# clock.net
KiCad netlist of a schematic drawn in Altium Designer
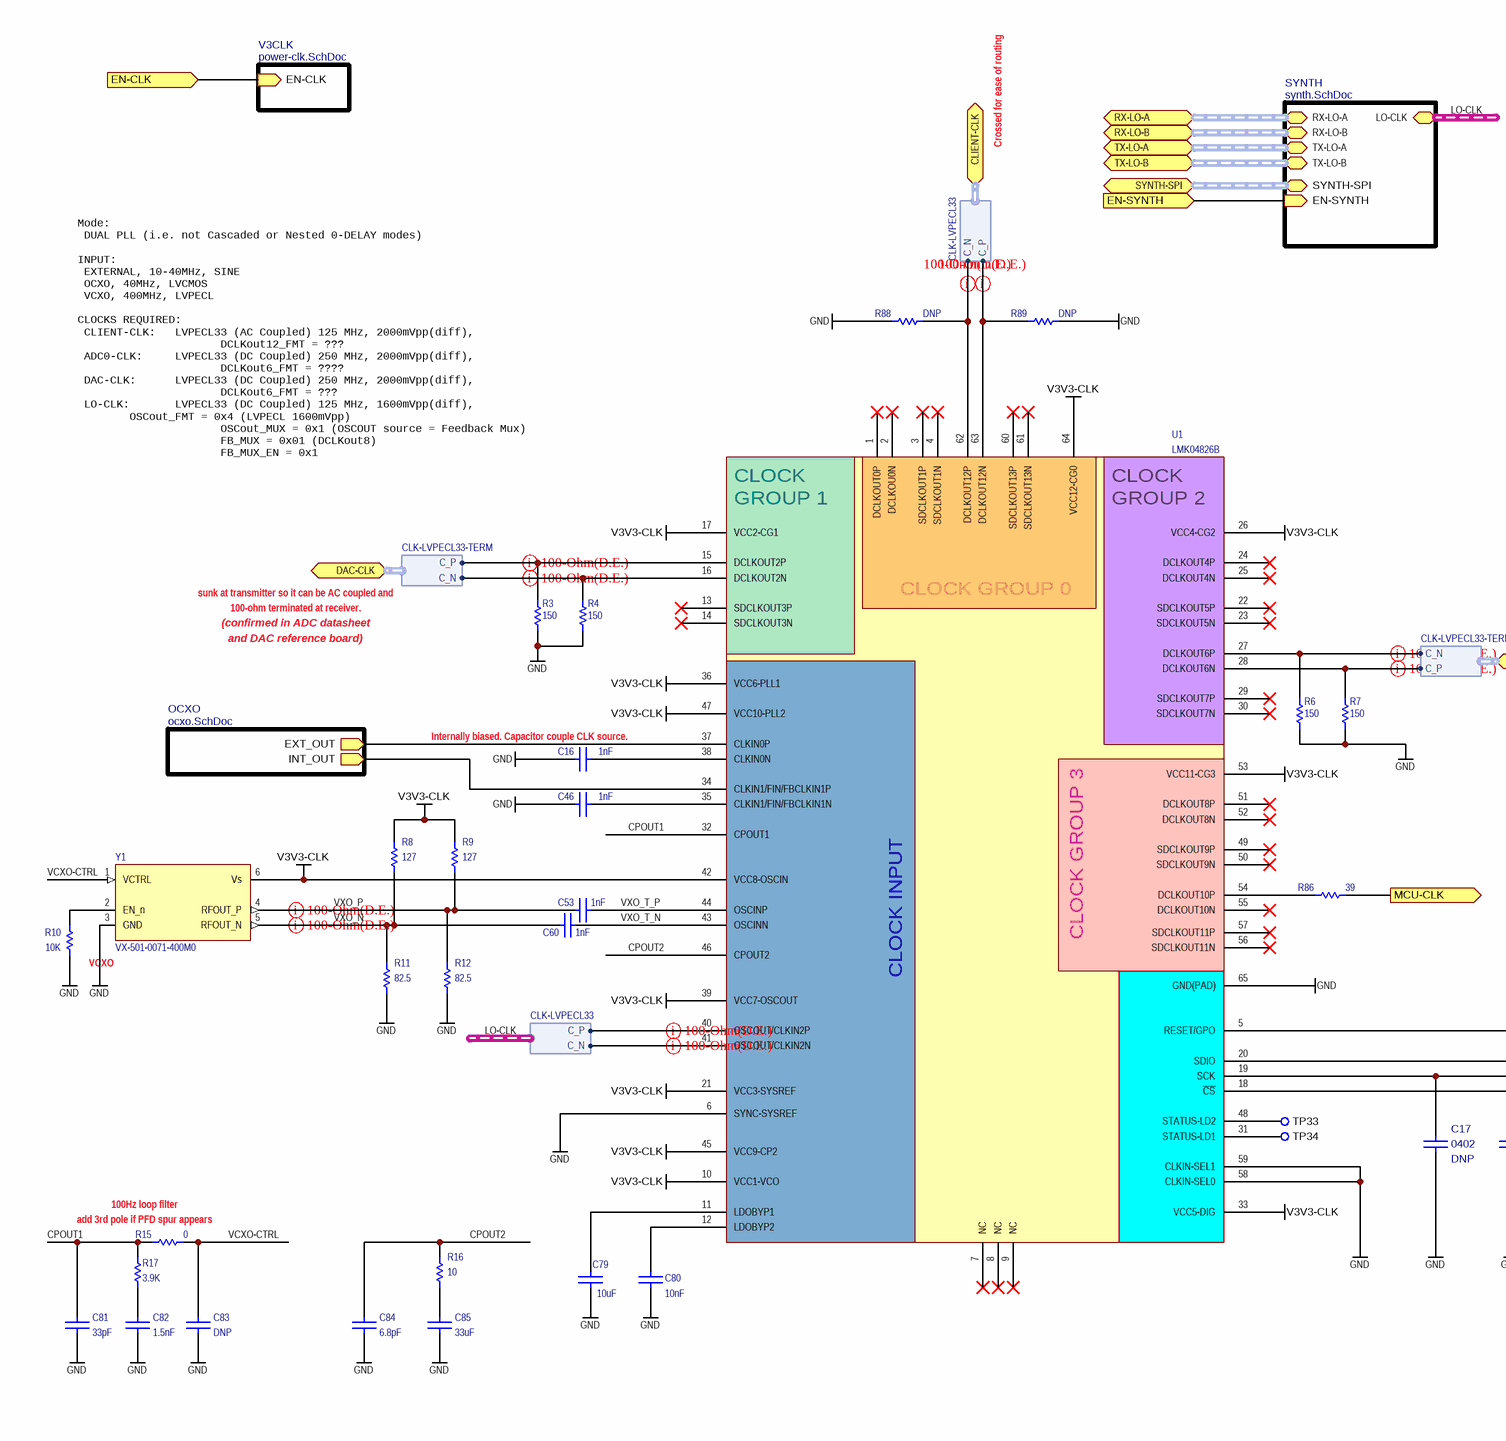
[diagram p0: clock.SchDoc, left]
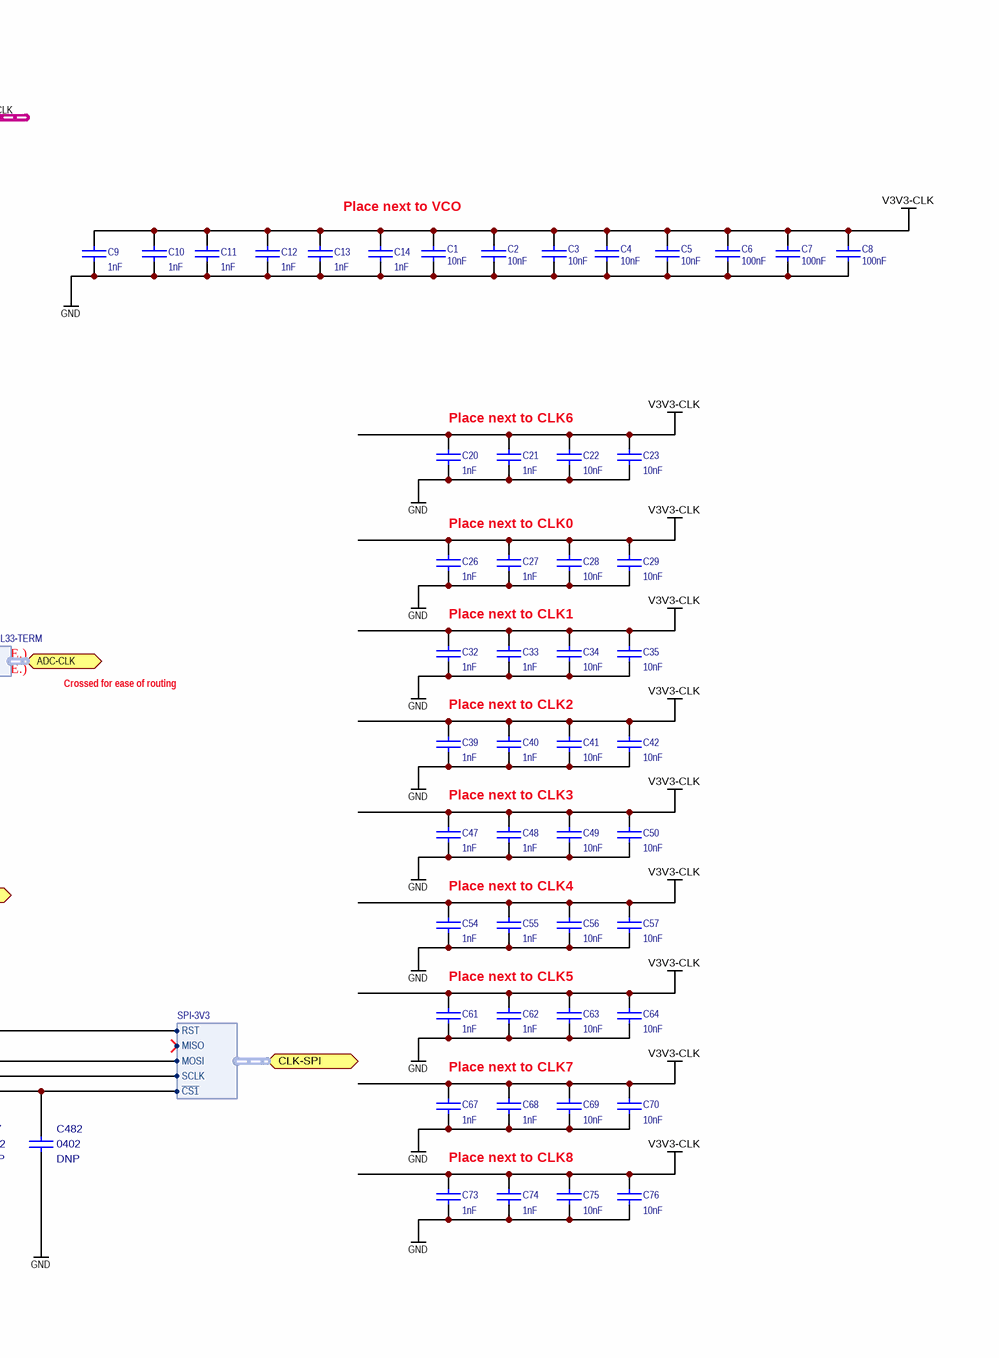
[diagram p1: clock.SchDoc, right]

(export (version "E")
  (design (tool "Eeschema 10.0.6"))
  (components
    (comp (ref "C1")
      (value "10nF")
      (footprint "CAPC100X50X55L25N")
      (description "Ceramic Capacitor 10nF ±10% 50V X7R 0402")
      (fields (field (name "VOLTAGE") "50V") (field (name "MANUFACTURER") "Murata"))
      (libsource (lib "Graviton") (part "CAP 0402"))
    )
    (comp (ref "C2")
      (value "10nF")
      (footprint "CAPC100X50X55L25N")
      (description "Ceramic Capacitor 10nF ±10% 50V X7R 0402")
      (fields (field (name "VOLTAGE") "50V") (field (name "MANUFACTURER") "Murata"))
      (libsource (lib "Graviton") (part "CAP 0402"))
    )
    (comp (ref "C3")
      (value "10nF")
      (footprint "CAPC100X50X55L25N")
      (description "Ceramic Capacitor 10nF ±10% 50V X7R 0402")
      (fields (field (name "VOLTAGE") "50V") (field (name "MANUFACTURER") "Murata"))
      (libsource (lib "Graviton") (part "CAP 0402"))
    )
    (comp (ref "C4")
      (value "10nF")
      (footprint "CAPC100X50X55L25N")
      (description "Ceramic Capacitor 10nF ±10% 50V X7R 0402")
      (fields (field (name "VOLTAGE") "50V") (field (name "MANUFACTURER") "Murata"))
      (libsource (lib "Graviton") (part "CAP 0402"))
    )
    (comp (ref "C5")
      (value "10nF")
      (footprint "CAPC100X50X55L25N")
      (description "Ceramic Capacitor 10nF ±10% 50V X7R 0402")
      (fields (field (name "VOLTAGE") "50V") (field (name "MANUFACTURER") "Murata"))
      (libsource (lib "Graviton") (part "CAP 0402"))
    )
    (comp (ref "C6")
      (value "100nF")
      (footprint "CAPC100X50X55L25N")
      (description "Ceramic Capacitor 100nF ±10% 16V X7R 0402")
      (fields (field (name "VOLTAGE") "16V") (field (name "MANUFACTURER") "Murata"))
      (libsource (lib "Graviton") (part "CAP 0402"))
    )
    (comp (ref "C7")
      (value "100nF")
      (footprint "CAPC100X50X55L25N")
      (description "Ceramic Capacitor 100nF ±10% 16V X7R 0402")
      (fields (field (name "VOLTAGE") "16V") (field (name "MANUFACTURER") "Murata"))
      (libsource (lib "Graviton") (part "CAP 0402"))
    )
    (comp (ref "C8")
      (value "100nF")
      (footprint "CAPC100X50X55L25N")
      (description "Ceramic Capacitor 100nF ±10% 16V X7R 0402")
      (fields (field (name "VOLTAGE") "16V") (field (name "MANUFACTURER") "Murata"))
      (libsource (lib "Graviton") (part "CAP 0402"))
    )
    (comp (ref "C9")
      (value "1nF")
      (footprint "CAPC100X50X55L25N")
      (description "Ceramic Capacitor 1nF ±5% 50V NP0 0402")
      (fields (field (name "VOLTAGE") "50V") (field (name "MANUFACTURER") "TDK"))
      (libsource (lib "Graviton") (part "CAP 0402"))
    )
    (comp (ref "C10")
      (value "1nF")
      (footprint "CAPC100X50X55L25N")
      (description "Ceramic Capacitor 1nF ±5% 50V NP0 0402")
      (fields (field (name "VOLTAGE") "50V") (field (name "MANUFACTURER") "TDK"))
      (libsource (lib "Graviton") (part "CAP 0402"))
    )
    (comp (ref "C11")
      (value "1nF")
      (footprint "CAPC100X50X55L25N")
      (description "Ceramic Capacitor 1nF ±5% 50V NP0 0402")
      (fields (field (name "VOLTAGE") "50V") (field (name "MANUFACTURER") "TDK"))
      (libsource (lib "Graviton") (part "CAP 0402"))
    )
    (comp (ref "C12")
      (value "1nF")
      (footprint "CAPC100X50X55L25N")
      (description "Ceramic Capacitor 1nF ±5% 50V NP0 0402")
      (fields (field (name "VOLTAGE") "50V") (field (name "MANUFACTURER") "TDK"))
      (libsource (lib "Graviton") (part "CAP 0402"))
    )
    (comp (ref "C13")
      (value "1nF")
      (footprint "CAPC100X50X55L25N")
      (description "Ceramic Capacitor 1nF ±5% 50V NP0 0402")
      (fields (field (name "VOLTAGE") "50V") (field (name "MANUFACTURER") "TDK"))
      (libsource (lib "Graviton") (part "CAP 0402"))
    )
    (comp (ref "C14")
      (value "1nF")
      (footprint "CAPC100X50X55L25N")
      (description "Ceramic Capacitor 1nF ±5% 50V NP0 0402")
      (fields (field (name "VOLTAGE") "50V") (field (name "MANUFACTURER") "TDK"))
      (libsource (lib "Graviton") (part "CAP 0402"))
    )
    (comp (ref "C16")
      (value "1nF")
      (footprint "CAPC100X50X55L25N")
      (description "Ceramic Capacitor 1nF ±5% 50V NP0 0402")
      (fields (field (name "VOLTAGE") "50V") (field (name "MANUFACTURER") "TDK"))
      (libsource (lib "Graviton") (part "CAP 0402"))
    )
    (comp (ref "C17")
      (value "VJ0402A101KXA")
      (footprint "CAPC100X50X55L25N")
      (description "Ceramic Capacitor 100pF ±10% 50V C0G 0402")
      (fields
        (field (name "MANUFACTURER") "Vishay")
        (field (name "TOLERANCE") "±10%")
        (field (name "PACKAGE") "0402")
        (field (name "DO NOT PLACE") "DNP")
      )
      (libsource (lib "capacitors") (part "CAP"))
    )
    (comp (ref "C20")
      (value "1nF")
      (footprint "CAPC100X50X55L25N")
      (description "Ceramic Capacitor 1nF ±5% 50V NP0 0402")
      (fields (field (name "VOLTAGE") "50V") (field (name "MANUFACTURER") "TDK"))
      (libsource (lib "Graviton") (part "CAP 0402"))
    )
    (comp (ref "C21")
      (value "1nF")
      (footprint "CAPC100X50X55L25N")
      (description "Ceramic Capacitor 1nF ±5% 50V NP0 0402")
      (fields (field (name "VOLTAGE") "50V") (field (name "MANUFACTURER") "TDK"))
      (libsource (lib "Graviton") (part "CAP 0402"))
    )
    (comp (ref "C22")
      (value "10nF")
      (footprint "CAPC100X50X55L25N")
      (description "Ceramic Capacitor 10nF ±10% 50V X7R 0402")
      (fields (field (name "VOLTAGE") "50V") (field (name "MANUFACTURER") "Murata"))
      (libsource (lib "Graviton") (part "CAP 0402"))
    )
    (comp (ref "C23")
      (value "10nF")
      (footprint "CAPC100X50X55L25N")
      (description "Ceramic Capacitor 10nF ±10% 50V X7R 0402")
      (fields (field (name "VOLTAGE") "50V") (field (name "MANUFACTURER") "Murata"))
      (libsource (lib "Graviton") (part "CAP 0402"))
    )
    (comp (ref "C26")
      (value "1nF")
      (footprint "CAPC100X50X55L25N")
      (description "Ceramic Capacitor 1nF ±5% 50V NP0 0402")
      (fields (field (name "VOLTAGE") "50V") (field (name "MANUFACTURER") "TDK"))
      (libsource (lib "Graviton") (part "CAP 0402"))
    )
    (comp (ref "C27")
      (value "1nF")
      (footprint "CAPC100X50X55L25N")
      (description "Ceramic Capacitor 1nF ±5% 50V NP0 0402")
      (fields (field (name "VOLTAGE") "50V") (field (name "MANUFACTURER") "TDK"))
      (libsource (lib "Graviton") (part "CAP 0402"))
    )
    (comp (ref "C28")
      (value "10nF")
      (footprint "CAPC100X50X55L25N")
      (description "Ceramic Capacitor 10nF ±10% 50V X7R 0402")
      (fields (field (name "VOLTAGE") "50V") (field (name "MANUFACTURER") "Murata"))
      (libsource (lib "Graviton") (part "CAP 0402"))
    )
    (comp (ref "C29")
      (value "10nF")
      (footprint "CAPC100X50X55L25N")
      (description "Ceramic Capacitor 10nF ±10% 50V X7R 0402")
      (fields (field (name "VOLTAGE") "50V") (field (name "MANUFACTURER") "Murata"))
      (libsource (lib "Graviton") (part "CAP 0402"))
    )
    (comp (ref "C32")
      (value "1nF")
      (footprint "CAPC100X50X55L25N")
      (description "Ceramic Capacitor 1nF ±5% 50V NP0 0402")
      (fields (field (name "VOLTAGE") "50V") (field (name "MANUFACTURER") "TDK"))
      (libsource (lib "Graviton") (part "CAP 0402"))
    )
    (comp (ref "C33")
      (value "1nF")
      (footprint "CAPC100X50X55L25N")
      (description "Ceramic Capacitor 1nF ±5% 50V NP0 0402")
      (fields (field (name "VOLTAGE") "50V") (field (name "MANUFACTURER") "TDK"))
      (libsource (lib "Graviton") (part "CAP 0402"))
    )
    (comp (ref "C34")
      (value "10nF")
      (footprint "CAPC100X50X55L25N")
      (description "Ceramic Capacitor 10nF ±10% 50V X7R 0402")
      (fields (field (name "VOLTAGE") "50V") (field (name "MANUFACTURER") "Murata"))
      (libsource (lib "Graviton") (part "CAP 0402"))
    )
    (comp (ref "C35")
      (value "10nF")
      (footprint "CAPC100X50X55L25N")
      (description "Ceramic Capacitor 10nF ±10% 50V X7R 0402")
      (fields (field (name "VOLTAGE") "50V") (field (name "MANUFACTURER") "Murata"))
      (libsource (lib "Graviton") (part "CAP 0402"))
    )
    (comp (ref "C39")
      (value "1nF")
      (footprint "CAPC100X50X55L25N")
      (description "Ceramic Capacitor 1nF ±5% 50V NP0 0402")
      (fields (field (name "VOLTAGE") "50V") (field (name "MANUFACTURER") "TDK"))
      (libsource (lib "Graviton") (part "CAP 0402"))
    )
    (comp (ref "C40")
      (value "1nF")
      (footprint "CAPC100X50X55L25N")
      (description "Ceramic Capacitor 1nF ±5% 50V NP0 0402")
      (fields (field (name "VOLTAGE") "50V") (field (name "MANUFACTURER") "TDK"))
      (libsource (lib "Graviton") (part "CAP 0402"))
    )
    (comp (ref "C41")
      (value "10nF")
      (footprint "CAPC100X50X55L25N")
      (description "Ceramic Capacitor 10nF ±10% 50V X7R 0402")
      (fields (field (name "VOLTAGE") "50V") (field (name "MANUFACTURER") "Murata"))
      (libsource (lib "Graviton") (part "CAP 0402"))
    )
    (comp (ref "C42")
      (value "10nF")
      (footprint "CAPC100X50X55L25N")
      (description "Ceramic Capacitor 10nF ±10% 50V X7R 0402")
      (fields (field (name "VOLTAGE") "50V") (field (name "MANUFACTURER") "Murata"))
      (libsource (lib "Graviton") (part "CAP 0402"))
    )
    (comp (ref "C46")
      (value "1nF")
      (footprint "CAPC100X50X55L25N")
      (description "Ceramic Capacitor 1nF ±5% 50V NP0 0402")
      (fields (field (name "VOLTAGE") "50V") (field (name "MANUFACTURER") "TDK"))
      (libsource (lib "Graviton") (part "CAP 0402"))
    )
    (comp (ref "C47")
      (value "1nF")
      (footprint "CAPC100X50X55L25N")
      (description "Ceramic Capacitor 1nF ±5% 50V NP0 0402")
      (fields (field (name "VOLTAGE") "50V") (field (name "MANUFACTURER") "TDK"))
      (libsource (lib "Graviton") (part "CAP 0402"))
    )
    (comp (ref "C48")
      (value "1nF")
      (footprint "CAPC100X50X55L25N")
      (description "Ceramic Capacitor 1nF ±5% 50V NP0 0402")
      (fields (field (name "VOLTAGE") "50V") (field (name "MANUFACTURER") "TDK"))
      (libsource (lib "Graviton") (part "CAP 0402"))
    )
    (comp (ref "C49")
      (value "10nF")
      (footprint "CAPC100X50X55L25N")
      (description "Ceramic Capacitor 10nF ±10% 50V X7R 0402")
      (fields (field (name "VOLTAGE") "50V") (field (name "MANUFACTURER") "Murata"))
      (libsource (lib "Graviton") (part "CAP 0402"))
    )
    (comp (ref "C50")
      (value "10nF")
      (footprint "CAPC100X50X55L25N")
      (description "Ceramic Capacitor 10nF ±10% 50V X7R 0402")
      (fields (field (name "VOLTAGE") "50V") (field (name "MANUFACTURER") "Murata"))
      (libsource (lib "Graviton") (part "CAP 0402"))
    )
    (comp (ref "C53")
      (value "1nF")
      (footprint "CAPC100X50X55L25N")
      (description "Ceramic Capacitor 1nF ±5% 50V NP0 0402")
      (fields (field (name "VOLTAGE") "50V") (field (name "MANUFACTURER") "TDK"))
      (libsource (lib "Graviton") (part "CAP 0402"))
    )
    (comp (ref "C54")
      (value "1nF")
      (footprint "CAPC100X50X55L25N")
      (description "Ceramic Capacitor 1nF ±5% 50V NP0 0402")
      (fields (field (name "VOLTAGE") "50V") (field (name "MANUFACTURER") "TDK"))
      (libsource (lib "Graviton") (part "CAP 0402"))
    )
    (comp (ref "C55")
      (value "1nF")
      (footprint "CAPC100X50X55L25N")
      (description "Ceramic Capacitor 1nF ±5% 50V NP0 0402")
      (fields (field (name "VOLTAGE") "50V") (field (name "MANUFACTURER") "TDK"))
      (libsource (lib "Graviton") (part "CAP 0402"))
    )
    (comp (ref "C56")
      (value "10nF")
      (footprint "CAPC100X50X55L25N")
      (description "Ceramic Capacitor 10nF ±10% 50V X7R 0402")
      (fields (field (name "VOLTAGE") "50V") (field (name "MANUFACTURER") "Murata"))
      (libsource (lib "Graviton") (part "CAP 0402"))
    )
    (comp (ref "C57")
      (value "10nF")
      (footprint "CAPC100X50X55L25N")
      (description "Ceramic Capacitor 10nF ±10% 50V X7R 0402")
      (fields (field (name "VOLTAGE") "50V") (field (name "MANUFACTURER") "Murata"))
      (libsource (lib "Graviton") (part "CAP 0402"))
    )
    (comp (ref "C60")
      (value "1nF")
      (footprint "CAPC100X50X55L25N")
      (description "Ceramic Capacitor 1nF ±5% 50V NP0 0402")
      (fields (field (name "VOLTAGE") "50V") (field (name "MANUFACTURER") "TDK"))
      (libsource (lib "Graviton") (part "CAP 0402"))
    )
    (comp (ref "C61")
      (value "1nF")
      (footprint "CAPC100X50X55L25N")
      (description "Ceramic Capacitor 1nF ±5% 50V NP0 0402")
      (fields (field (name "VOLTAGE") "50V") (field (name "MANUFACTURER") "TDK"))
      (libsource (lib "Graviton") (part "CAP 0402"))
    )
    (comp (ref "C62")
      (value "1nF")
      (footprint "CAPC100X50X55L25N")
      (description "Ceramic Capacitor 1nF ±5% 50V NP0 0402")
      (fields (field (name "VOLTAGE") "50V") (field (name "MANUFACTURER") "TDK"))
      (libsource (lib "Graviton") (part "CAP 0402"))
    )
    (comp (ref "C63")
      (value "10nF")
      (footprint "CAPC100X50X55L25N")
      (description "Ceramic Capacitor 10nF ±10% 50V X7R 0402")
      (fields (field (name "VOLTAGE") "50V") (field (name "MANUFACTURER") "Murata"))
      (libsource (lib "Graviton") (part "CAP 0402"))
    )
    (comp (ref "C64")
      (value "10nF")
      (footprint "CAPC100X50X55L25N")
      (description "Ceramic Capacitor 10nF ±10% 50V X7R 0402")
      (fields (field (name "VOLTAGE") "50V") (field (name "MANUFACTURER") "Murata"))
      (libsource (lib "Graviton") (part "CAP 0402"))
    )
    (comp (ref "C67")
      (value "1nF")
      (footprint "CAPC100X50X55L25N")
      (description "Ceramic Capacitor 1nF ±5% 50V NP0 0402")
      (fields (field (name "VOLTAGE") "50V") (field (name "MANUFACTURER") "TDK"))
      (libsource (lib "Graviton") (part "CAP 0402"))
    )
    (comp (ref "C68")
      (value "1nF")
      (footprint "CAPC100X50X55L25N")
      (description "Ceramic Capacitor 1nF ±5% 50V NP0 0402")
      (fields (field (name "VOLTAGE") "50V") (field (name "MANUFACTURER") "TDK"))
      (libsource (lib "Graviton") (part "CAP 0402"))
    )
    (comp (ref "C69")
      (value "10nF")
      (footprint "CAPC100X50X55L25N")
      (description "Ceramic Capacitor 10nF ±10% 50V X7R 0402")
      (fields (field (name "VOLTAGE") "50V") (field (name "MANUFACTURER") "Murata"))
      (libsource (lib "Graviton") (part "CAP 0402"))
    )
    (comp (ref "C70")
      (value "10nF")
      (footprint "CAPC100X50X55L25N")
      (description "Ceramic Capacitor 10nF ±10% 50V X7R 0402")
      (fields (field (name "VOLTAGE") "50V") (field (name "MANUFACTURER") "Murata"))
      (libsource (lib "Graviton") (part "CAP 0402"))
    )
    (comp (ref "C73")
      (value "1nF")
      (footprint "CAPC100X50X55L25N")
      (description "Ceramic Capacitor 1nF ±5% 50V NP0 0402")
      (fields (field (name "VOLTAGE") "50V") (field (name "MANUFACTURER") "TDK"))
      (libsource (lib "Graviton") (part "CAP 0402"))
    )
    (comp (ref "C74")
      (value "1nF")
      (footprint "CAPC100X50X55L25N")
      (description "Ceramic Capacitor 1nF ±5% 50V NP0 0402")
      (fields (field (name "VOLTAGE") "50V") (field (name "MANUFACTURER") "TDK"))
      (libsource (lib "Graviton") (part "CAP 0402"))
    )
    (comp (ref "C75")
      (value "10nF")
      (footprint "CAPC100X50X55L25N")
      (description "Ceramic Capacitor 10nF ±10% 50V X7R 0402")
      (fields (field (name "VOLTAGE") "50V") (field (name "MANUFACTURER") "Murata"))
      (libsource (lib "Graviton") (part "CAP 0402"))
    )
    (comp (ref "C76")
      (value "10nF")
      (footprint "CAPC100X50X55L25N")
      (description "Ceramic Capacitor 10nF ±10% 50V X7R 0402")
      (fields (field (name "VOLTAGE") "50V") (field (name "MANUFACTURER") "Murata"))
      (libsource (lib "Graviton") (part "CAP 0402"))
    )
    (comp (ref "C79")
      (value "10uF")
      (footprint "CAPC160X80X90L20N")
      (description "Ceramic Capacitor 10uF ±20% 25V X5R 0603")
      (fields (field (name "MANUFACTURER") "Murata") (field (name "TOLERANCE") "±20%"))
      (libsource (lib "generic") (part "CAP"))
    )
    (comp (ref "C80")
      (value "10nF")
      (footprint "CAPC100X50X55L25N")
      (description "Ceramic Capacitor 10nF ±10% 50V X7R 0402")
      (fields (field (name "VOLTAGE") "50V") (field (name "MANUFACTURER") "Murata"))
      (libsource (lib "Graviton") (part "CAP 0402"))
    )
    (comp (ref "C81")
      (value "33pF")
      (footprint "CAPC100X50X55L25N")
      (description "Ceramic Capacitor 33pF ±5% 50V NP0 0402")
      (fields (field (name "VOLTAGE") "50V") (field (name "MANUFACTURER") "Murata"))
      (libsource (lib "Graviton") (part "CAP 0402"))
    )
    (comp (ref "C82")
      (value "1.5nF")
      (footprint "CAPC100X50X55L25N")
      (description "Ceramic Capacitor 1.5nF ±10% 16V RF 0402")
      (fields (field (name "VOLTAGE") "16V") (field (name "MANUFACTURER") "Taiyo Yuden"))
      (libsource (lib "Graviton") (part "CAP 0402"))
    )
    (comp (ref "C83")
      (value "CGA2B2NP01H102J050BA")
      (footprint "CAPC100X50X55L25N")
      (description "Ceramic Capacitor 1nF ±5% 50V NP0 0402")
      (fields
        (field (name "VOLTAGE") "50V")
        (field (name "MANUFACTURER") "TDK")
        (field (name "DO NOT PLACE") "DNP")
      )
      (libsource (lib "Graviton") (part "CAP 0402"))
    )
    (comp (ref "C84")
      (value "6.8pF")
      (footprint "CAPC160X80X90L20N")
      (description "Ceramic Capacitor 6.8pF ±0.1pF NP0 0603")
      (fields (field (name "VOLTAGE") "200V") (field (name "MANUFACTURER") "AVX"))
      (libsource (lib "Graviton") (part "CAP 0402"))
    )
    (comp (ref "C85")
      (value "33uF")
      (footprint "CAPC2012X145N")
      (description "Ceramic Capacitor 33uF ±20% 10V X5R 0805")
      (fields (field (name "VOLTAGE") "10V") (field (name "MANUFACTURER") "TDK"))
      (libsource (lib "Graviton") (part "CAP 0402"))
    )
    (comp (ref "C482")
      (value "VJ0402A101KXA")
      (footprint "CAPC100X50X55L25N")
      (description "Ceramic Capacitor 100pF ±10% 50V C0G 0402")
      (fields
        (field (name "MANUFACTURER") "Vishay")
        (field (name "TOLERANCE") "±10%")
        (field (name "PACKAGE") "0402")
        (field (name "DO NOT PLACE") "DNP")
      )
      (libsource (lib "capacitors") (part "CAP"))
    )
    (comp (ref "R3")
      (value "150")
      (footprint "RESC1005X40N")
      (description "Thick Film 150 ±1% 0402")
      (fields (field (name "MANUFACTURER") "Panasonic") (field (name "TOLERANCE") "±1%"))
      (libsource (lib "Graviton") (part "RES 0402"))
    )
    (comp (ref "R4")
      (value "150")
      (footprint "RESC1005X40N")
      (description "Thick Film 150 ±1% 0402")
      (fields (field (name "MANUFACTURER") "Panasonic") (field (name "TOLERANCE") "±1%"))
      (libsource (lib "Graviton") (part "RES 0402"))
    )
    (comp (ref "R6")
      (value "150")
      (footprint "RESC1005X40N")
      (description "Thick Film 150 ±1% 0402")
      (fields (field (name "MANUFACTURER") "Panasonic") (field (name "TOLERANCE") "±1%"))
      (libsource (lib "Graviton") (part "RES 0402"))
    )
    (comp (ref "R7")
      (value "150")
      (footprint "RESC1005X40N")
      (description "Thick Film 150 ±1% 0402")
      (fields (field (name "MANUFACTURER") "Panasonic") (field (name "TOLERANCE") "±1%"))
      (libsource (lib "Graviton") (part "RES 0402"))
    )
    (comp (ref "R8")
      (value "127")
      (footprint "RESC1005X40N")
      (description "Thin Film Resistor 127 ±0.1% 0402")
      (fields (field (name "MANUFACTURER") "Panasonic") (field (name "TOLERANCE") "±0.1%"))
      (libsource (lib "Graviton") (part "RES 0402"))
    )
    (comp (ref "R9")
      (value "127")
      (footprint "RESC1005X40N")
      (description "Thin Film Resistor 127 ±0.1% 0402")
      (fields (field (name "MANUFACTURER") "Panasonic") (field (name "TOLERANCE") "±0.1%"))
      (libsource (lib "Graviton") (part "RES 0402"))
    )
    (comp (ref "R10")
      (value "10K")
      (footprint "RESC1005X40N")
      (description "Thick Film Resistor 10k ±1% 0.1W 50V 0402")
      (fields (field (name "MANUFACTURER") "Panasonic") (field (name "TOLERANCE") "±1%"))
      (libsource (lib "Graviton") (part "RES 0402"))
    )
    (comp (ref "R11")
      (value "82.5")
      (footprint "RESC1005X40N")
      (description "Thin Film Resistor 82.5 ±0.1% 0402")
      (fields (field (name "MANUFACTURER") "Panasonic") (field (name "TOLERANCE") "±0.1%"))
      (libsource (lib "Graviton") (part "RES 0402"))
    )
    (comp (ref "R12")
      (value "82.5")
      (footprint "RESC1005X40N")
      (description "Thin Film Resistor 82.5 ±0.1% 0402")
      (fields (field (name "MANUFACTURER") "Panasonic") (field (name "TOLERANCE") "±0.1%"))
      (libsource (lib "Graviton") (part "RES 0402"))
    )
    (comp (ref "R15")
      (value "0")
      (footprint "RESC1005X40N")
      (description "Thick Film Resistor Jumper 0402")
      (fields (field (name "MANUFACTURER") "Panasonic") (field (name "Comment") "ERJ-2GE0R00X"))
      (libsource (lib "Graviton") (part "RES 0603"))
    )
    (comp (ref "R16")
      (value "10")
      (footprint "RESC1005X40N")
      (description "Thin Film Resistor 10 Ohm ±1% 0402")
      (fields (field (name "MANUFACTURER") "Vishay") (field (name "TOLERANCE") "±1%"))
      (libsource (lib "Graviton") (part "RES 0402"))
    )
    (comp (ref "R17")
      (value "3.9K")
      (footprint "RESC1608X55N")
      (description "Thin Film Resistor 3.9k ±0.1% 0603")
      (fields (field (name "MANUFACTURER") "Panasonic") (field (name "TOLERANCE") "±0.1%"))
      (libsource (lib "Graviton") (part "RES 0603"))
    )
    (comp (ref "R86")
      (value "39")
      (footprint "RESC1005X40N")
      (description "Thick Film Resistor 39 ±1% 0402")
      (fields (field (name "MANUFACTURER") "Yageo") (field (name "TOLERANCE") "±1%"))
      (libsource (lib "Graviton") (part "RES 0402"))
    )
    (comp (ref "R88")
      (value "ERJ-2RKF1500X")
      (footprint "RESC1005X40N")
      (description "Thick Film 150 ±1% 0402")
      (fields
        (field (name "MANUFACTURER") "Panasonic")
        (field (name "DO NOT PLACE") "DNP")
        (field (name "TOLERANCE") "±1%")
      )
      (libsource (lib "Graviton") (part "RES 0402"))
    )
    (comp (ref "R89")
      (value "ERJ-2RKF1500X")
      (footprint "RESC1005X40N")
      (description "Thick Film 150 ±1% 0402")
      (fields
        (field (name "MANUFACTURER") "Panasonic")
        (field (name "DO NOT PLACE") "DNP")
        (field (name "TOLERANCE") "±1%")
      )
      (libsource (lib "Graviton") (part "RES 0402"))
    )
    (comp (ref "TP33")
      (value "TEST_POINT_SMD_50")
      (footprint "generic:TEST_POINT_SMD_10")
      (description "Test Point SMD")
      (libsource (lib "generic") (part "TEST_POINT_SMD_50"))
    )
    (comp (ref "TP34")
      (value "TEST_POINT_SMD_50")
      (footprint "generic:TEST_POINT_SMD_10")
      (description "Test Point SMD")
      (libsource (lib "generic") (part "TEST_POINT_SMD_50"))
    )
    (comp (ref "U1")
      (value "LMK04826B")
      (footprint "texas_instruments:NKD0064A")
      (description "Low-Noise Clock Jitter Cleaner with Dual Loop PLLs")
      (fields (field (name "MANUFACTURER") "Texas Instruments"))
      (libsource (lib "ti") (part "LMK04828"))
    )
    (comp (ref "Y1")
      (value "VX-501-0071-400M0")
      (footprint "G218")
      (description "VCXO, Ultra Low Phase Noise, 490MHz")
      (fields (field (name "MANUFACTURER") "Vectron"))
      (libsource (lib "vectron") (part "VX-501"))
    )
  )
  (nets
    (net (code "11") (name "/CPOUT1") (class "Default")
      (node (ref "C81") (pin "1") (pinfunction "1_1") (pintype "passive"))
      (node (ref "R15") (pin "1") (pinfunction "1_1") (pintype "passive"))
      (node (ref "R17") (pin "2") (pinfunction "2_2") (pintype "passive"))
      (node (ref "U1") (pin "32") (pinfunction "CPOUT1_32") (pintype "passive"))
    )
    (net (code "12") (name "/CPOUT2") (class "Default")
      (node (ref "C84") (pin "1") (pinfunction "1_1") (pintype "passive"))
      (node (ref "R16") (pin "2") (pinfunction "2_2") (pintype "passive"))
      (node (ref "U1") (pin "46") (pinfunction "CPOUT2_46") (pintype "passive"))
    )
    (net (code "15") (name "/EXT_OUT") (class "Default")
      (node (ref "U1") (pin "37") (pinfunction "CLKIN0P_37") (pintype "passive"))
    )
    (net (code "16") (name "/INT_OUT") (class "Default")
      (node (ref "U1") (pin "34") (pinfunction "CLKIN1/FIN/FBCLKIN1P_34") (pintype "passive"))
    )
    (net (code "18") (name "/MCU-CLK") (class "Default")
      (node (ref "R86") (pin "2") (pinfunction "2_2") (pintype "passive"))
    )
    (net (code "19") (name "/MOSI") (class "Default")
      (node (ref "U1") (pin "20") (pinfunction "SDIO_20") (pintype "passive"))
    )
    (net (code "20") (name "/RST") (class "Default")
      (node (ref "U1") (pin "5") (pinfunction "RESET/GPO_5") (pintype "passive"))
    )
    (net (code "23") (name "/SCLK") (class "Default")
      (node (ref "C17") (pin "1") (pinfunction "1_1") (pintype "passive"))
      (node (ref "U1") (pin "19") (pinfunction "SCK_19") (pintype "passive"))
    )
    (net (code "27") (name "/VCXO-CTRL") (class "Default")
      (node (ref "C83") (pin "1") (pinfunction "1_1") (pintype "passive"))
      (node (ref "R15") (pin "2") (pinfunction "2_2") (pintype "passive"))
      (node (ref "Y1") (pin "1") (pinfunction "VCTRL_1") (pintype "input"))
    )
    (net (code "28") (name "/VXO_N") (class "Default")
      (node (ref "C60") (pin "1") (pinfunction "1_1") (pintype "passive"))
      (node (ref "R11") (pin "2") (pinfunction "2_2") (pintype "passive"))
      (node (ref "R8") (pin "1") (pinfunction "1_1") (pintype "passive"))
      (node (ref "Y1") (pin "5") (pinfunction "RFOUT_N_5") (pintype "output"))
    )
    (net (code "29") (name "/VXO_P") (class "Default")
      (node (ref "C53") (pin "2") (pinfunction "2_2") (pintype "passive"))
      (node (ref "R12") (pin "2") (pinfunction "2_2") (pintype "passive"))
      (node (ref "R9") (pin "1") (pinfunction "1_1") (pintype "passive"))
      (node (ref "Y1") (pin "4") (pinfunction "RFOUT_P_4") (pintype "output"))
    )
    (net (code "30") (name "/VXO_T_N") (class "Default")
      (node (ref "C60") (pin "2") (pinfunction "2_2") (pintype "passive"))
      (node (ref "U1") (pin "43") (pinfunction "OSCINN_43") (pintype "passive"))
    )
    (net (code "31") (name "/VXO_T_P") (class "Default")
      (node (ref "C53") (pin "1") (pinfunction "1_1") (pintype "passive"))
      (node (ref "U1") (pin "44") (pinfunction "OSCINP_44") (pintype "passive"))
    )
    (net (code "36") (name "/~{CS1}") (class "Default")
      (node (ref "C482") (pin "1") (pinfunction "1_1") (pintype "passive"))
      (node (ref "U1") (pin "18") (pinfunction "~{CS}_18") (pintype "passive"))
    )
    (net (code "37") (name "GND") (class "Default")
      (node (ref "C1") (pin "1") (pinfunction "1_1") (pintype "passive"))
      (node (ref "C10") (pin "1") (pinfunction "1_1") (pintype "passive"))
      (node (ref "C11") (pin "1") (pinfunction "1_1") (pintype "passive"))
      (node (ref "C12") (pin "1") (pinfunction "1_1") (pintype "passive"))
      (node (ref "C13") (pin "1") (pinfunction "1_1") (pintype "passive"))
      (node (ref "C14") (pin "1") (pinfunction "1_1") (pintype "passive"))
      (node (ref "C16") (pin "2") (pinfunction "2_2") (pintype "passive"))
      (node (ref "C17") (pin "2") (pinfunction "2_2") (pintype "passive"))
      (node (ref "C2") (pin "1") (pinfunction "1_1") (pintype "passive"))
      (node (ref "C20") (pin "1") (pinfunction "1_1") (pintype "passive"))
      (node (ref "C21") (pin "1") (pinfunction "1_1") (pintype "passive"))
      (node (ref "C22") (pin "1") (pinfunction "1_1") (pintype "passive"))
      (node (ref "C23") (pin "1") (pinfunction "1_1") (pintype "passive"))
      (node (ref "C26") (pin "1") (pinfunction "1_1") (pintype "passive"))
      (node (ref "C27") (pin "1") (pinfunction "1_1") (pintype "passive"))
      (node (ref "C28") (pin "1") (pinfunction "1_1") (pintype "passive"))
      (node (ref "C29") (pin "1") (pinfunction "1_1") (pintype "passive"))
      (node (ref "C3") (pin "1") (pinfunction "1_1") (pintype "passive"))
      (node (ref "C32") (pin "1") (pinfunction "1_1") (pintype "passive"))
      (node (ref "C33") (pin "1") (pinfunction "1_1") (pintype "passive"))
      (node (ref "C34") (pin "1") (pinfunction "1_1") (pintype "passive"))
      (node (ref "C35") (pin "1") (pinfunction "1_1") (pintype "passive"))
      (node (ref "C39") (pin "1") (pinfunction "1_1") (pintype "passive"))
      (node (ref "C4") (pin "1") (pinfunction "1_1") (pintype "passive"))
      (node (ref "C40") (pin "1") (pinfunction "1_1") (pintype "passive"))
      (node (ref "C41") (pin "1") (pinfunction "1_1") (pintype "passive"))
      (node (ref "C42") (pin "1") (pinfunction "1_1") (pintype "passive"))
      (node (ref "C46") (pin "2") (pinfunction "2_2") (pintype "passive"))
      (node (ref "C47") (pin "1") (pinfunction "1_1") (pintype "passive"))
      (node (ref "C48") (pin "1") (pinfunction "1_1") (pintype "passive"))
      (node (ref "C482") (pin "2") (pinfunction "2_2") (pintype "passive"))
      (node (ref "C49") (pin "1") (pinfunction "1_1") (pintype "passive"))
      (node (ref "C5") (pin "1") (pinfunction "1_1") (pintype "passive"))
      (node (ref "C50") (pin "1") (pinfunction "1_1") (pintype "passive"))
      (node (ref "C54") (pin "1") (pinfunction "1_1") (pintype "passive"))
      (node (ref "C55") (pin "1") (pinfunction "1_1") (pintype "passive"))
      (node (ref "C56") (pin "1") (pinfunction "1_1") (pintype "passive"))
      (node (ref "C57") (pin "1") (pinfunction "1_1") (pintype "passive"))
      (node (ref "C6") (pin "1") (pinfunction "1_1") (pintype "passive"))
      (node (ref "C61") (pin "1") (pinfunction "1_1") (pintype "passive"))
      (node (ref "C62") (pin "1") (pinfunction "1_1") (pintype "passive"))
      (node (ref "C63") (pin "1") (pinfunction "1_1") (pintype "passive"))
      (node (ref "C64") (pin "1") (pinfunction "1_1") (pintype "passive"))
      (node (ref "C67") (pin "1") (pinfunction "1_1") (pintype "passive"))
      (node (ref "C68") (pin "1") (pinfunction "1_1") (pintype "passive"))
      (node (ref "C69") (pin "1") (pinfunction "1_1") (pintype "passive"))
      (node (ref "C7") (pin "1") (pinfunction "1_1") (pintype "passive"))
      (node (ref "C70") (pin "1") (pinfunction "1_1") (pintype "passive"))
      (node (ref "C73") (pin "1") (pinfunction "1_1") (pintype "passive"))
      (node (ref "C74") (pin "1") (pinfunction "1_1") (pintype "passive"))
      (node (ref "C75") (pin "1") (pinfunction "1_1") (pintype "passive"))
      (node (ref "C76") (pin "1") (pinfunction "1_1") (pintype "passive"))
      (node (ref "C79") (pin "1") (pinfunction "1_1") (pintype "passive"))
      (node (ref "C8") (pin "1") (pinfunction "1_1") (pintype "passive"))
      (node (ref "C80") (pin "1") (pinfunction "1_1") (pintype "passive"))
      (node (ref "C81") (pin "2") (pinfunction "2_2") (pintype "passive"))
      (node (ref "C82") (pin "2") (pinfunction "2_2") (pintype "passive"))
      (node (ref "C83") (pin "2") (pinfunction "2_2") (pintype "passive"))
      (node (ref "C84") (pin "2") (pinfunction "2_2") (pintype "passive"))
      (node (ref "C85") (pin "2") (pinfunction "2_2") (pintype "passive"))
      (node (ref "C9") (pin "1") (pinfunction "1_1") (pintype "passive"))
      (node (ref "R10") (pin "2") (pinfunction "2_2") (pintype "passive"))
      (node (ref "R11") (pin "1") (pinfunction "1_1") (pintype "passive"))
      (node (ref "R12") (pin "1") (pinfunction "1_1") (pintype "passive"))
      (node (ref "R3") (pin "2") (pinfunction "2_2") (pintype "passive"))
      (node (ref "R4") (pin "2") (pinfunction "2_2") (pintype "passive"))
      (node (ref "R6") (pin "1") (pinfunction "1_1") (pintype "passive"))
      (node (ref "R7") (pin "1") (pinfunction "1_1") (pintype "passive"))
      (node (ref "R88") (pin "2") (pinfunction "2_2") (pintype "passive"))
      (node (ref "R89") (pin "1") (pinfunction "1_1") (pintype "passive"))
      (node (ref "U1") (pin "58") (pinfunction "CLKIN-SEL0_58") (pintype "passive"))
      (node (ref "U1") (pin "59") (pinfunction "CLKIN-SEL1_59") (pintype "passive"))
      (node (ref "U1") (pin "6") (pinfunction "SYNC-SYSREF_6") (pintype "passive"))
      (node (ref "U1") (pin "65") (pinfunction "GND(PAD)_65") (pintype "passive"))
      (node (ref "Y1") (pin "3") (pinfunction "GND_3") (pintype "power_in"))
    )
    (net (code "38") (name "Net-(C82-Pad1)") (class "Default")
      (node (ref "C82") (pin "1") (pinfunction "1_1") (pintype "passive"))
      (node (ref "R17") (pin "1") (pinfunction "1_1") (pintype "passive"))
    )
    (net (code "39") (name "Net-(C85-Pad1)") (class "Default")
      (node (ref "C85") (pin "1") (pinfunction "1_1") (pintype "passive"))
      (node (ref "R16") (pin "1") (pinfunction "1_1") (pintype "passive"))
    )
    (net (code "40") (name "Net-(U1-CLKIN0N)") (class "Default")
      (node (ref "C16") (pin "1") (pinfunction "1_1") (pintype "passive"))
      (node (ref "U1") (pin "38") (pinfunction "CLKIN0N_38") (pintype "passive"))
    )
    (net (code "41") (name "Net-(U1-CLKIN1{slash}FIN{slash}FBCLKIN1N)") (class "Default")
      (node (ref "C46") (pin "1") (pinfunction "1_1") (pintype "passive"))
      (node (ref "U1") (pin "35") (pinfunction "CLKIN1/FIN/FBCLKIN1N_35") (pintype "passive"))
    )
    (net (code "42") (name "Net-(U1-DCLKOUT2N)") (class "Default")
      (node (ref "R4") (pin "1") (pinfunction "1_1") (pintype "passive"))
      (node (ref "U1") (pin "16") (pinfunction "DCLKOUT2N_16") (pintype "passive"))
    )
    (net (code "43") (name "Net-(U1-DCLKOUT2P)") (class "Default")
      (node (ref "R3") (pin "1") (pinfunction "1_1") (pintype "passive"))
      (node (ref "U1") (pin "15") (pinfunction "DCLKOUT2P_15") (pintype "passive"))
    )
    (net (code "44") (name "Net-(U1-DCLKOUT6N)") (class "Default")
      (node (ref "R7") (pin "2") (pinfunction "2_2") (pintype "passive"))
      (node (ref "U1") (pin "28") (pinfunction "DCLKOUT6N_28") (pintype "passive"))
    )
    (net (code "45") (name "Net-(U1-DCLKOUT6P)") (class "Default")
      (node (ref "R6") (pin "2") (pinfunction "2_2") (pintype "passive"))
      (node (ref "U1") (pin "27") (pinfunction "DCLKOUT6P_27") (pintype "passive"))
    )
    (net (code "46") (name "Net-(U1-DCLKOUT10P)") (class "Default")
      (node (ref "R86") (pin "1") (pinfunction "1_1") (pintype "passive"))
      (node (ref "U1") (pin "54") (pinfunction "DCLKOUT10P_54") (pintype "passive"))
    )
    (net (code "47") (name "Net-(U1-DCLKOUT12N)") (class "Default")
      (node (ref "R89") (pin "2") (pinfunction "2_2") (pintype "passive"))
      (node (ref "U1") (pin "63") (pinfunction "DCLKOUT12N_63") (pintype "passive"))
    )
    (net (code "48") (name "Net-(U1-DCLKOUT12P)") (class "Default")
      (node (ref "R88") (pin "1") (pinfunction "1_1") (pintype "passive"))
      (node (ref "U1") (pin "62") (pinfunction "DCLKOUT12P_62") (pintype "passive"))
    )
    (net (code "49") (name "Net-(U1-LDOBYP1)") (class "Default")
      (node (ref "C79") (pin "2") (pinfunction "2_2") (pintype "passive"))
      (node (ref "U1") (pin "11") (pinfunction "LDOBYP1_11") (pintype "passive"))
    )
    (net (code "50") (name "Net-(U1-LDOBYP2)") (class "Default")
      (node (ref "C80") (pin "2") (pinfunction "2_2") (pintype "passive"))
      (node (ref "U1") (pin "12") (pinfunction "LDOBYP2_12") (pintype "passive"))
    )
    (net (code "51") (name "Net-(U1-STATUS-LD1)") (class "Default")
      (node (ref "TP34") (pin "1") (pinfunction "1_1") (pintype "passive"))
      (node (ref "U1") (pin "31") (pinfunction "STATUS-LD1_31") (pintype "passive"))
    )
    (net (code "52") (name "Net-(U1-STATUS-LD2)") (class "Default")
      (node (ref "TP33") (pin "1") (pinfunction "1_1") (pintype "passive"))
      (node (ref "U1") (pin "48") (pinfunction "STATUS-LD2_48") (pintype "passive"))
    )
    (net (code "53") (name "Net-(Y1-EN_n)") (class "Default")
      (node (ref "R10") (pin "1") (pinfunction "1_1") (pintype "passive"))
      (node (ref "Y1") (pin "2") (pinfunction "EN_n_2") (pintype "power_in"))
    )
    (net (code "54") (name "V3V3-CLK") (class "Default")
      (node (ref "C1") (pin "2") (pinfunction "2_2") (pintype "passive"))
      (node (ref "C10") (pin "2") (pinfunction "2_2") (pintype "passive"))
      (node (ref "C11") (pin "2") (pinfunction "2_2") (pintype "passive"))
      (node (ref "C12") (pin "2") (pinfunction "2_2") (pintype "passive"))
      (node (ref "C13") (pin "2") (pinfunction "2_2") (pintype "passive"))
      (node (ref "C14") (pin "2") (pinfunction "2_2") (pintype "passive"))
      (node (ref "C2") (pin "2") (pinfunction "2_2") (pintype "passive"))
      (node (ref "C20") (pin "2") (pinfunction "2_2") (pintype "passive"))
      (node (ref "C21") (pin "2") (pinfunction "2_2") (pintype "passive"))
      (node (ref "C22") (pin "2") (pinfunction "2_2") (pintype "passive"))
      (node (ref "C23") (pin "2") (pinfunction "2_2") (pintype "passive"))
      (node (ref "C26") (pin "2") (pinfunction "2_2") (pintype "passive"))
      (node (ref "C27") (pin "2") (pinfunction "2_2") (pintype "passive"))
      (node (ref "C28") (pin "2") (pinfunction "2_2") (pintype "passive"))
      (node (ref "C29") (pin "2") (pinfunction "2_2") (pintype "passive"))
      (node (ref "C3") (pin "2") (pinfunction "2_2") (pintype "passive"))
      (node (ref "C32") (pin "2") (pinfunction "2_2") (pintype "passive"))
      (node (ref "C33") (pin "2") (pinfunction "2_2") (pintype "passive"))
      (node (ref "C34") (pin "2") (pinfunction "2_2") (pintype "passive"))
      (node (ref "C35") (pin "2") (pinfunction "2_2") (pintype "passive"))
      (node (ref "C39") (pin "2") (pinfunction "2_2") (pintype "passive"))
      (node (ref "C4") (pin "2") (pinfunction "2_2") (pintype "passive"))
      (node (ref "C40") (pin "2") (pinfunction "2_2") (pintype "passive"))
      (node (ref "C41") (pin "2") (pinfunction "2_2") (pintype "passive"))
      (node (ref "C42") (pin "2") (pinfunction "2_2") (pintype "passive"))
      (node (ref "C47") (pin "2") (pinfunction "2_2") (pintype "passive"))
      (node (ref "C48") (pin "2") (pinfunction "2_2") (pintype "passive"))
      (node (ref "C49") (pin "2") (pinfunction "2_2") (pintype "passive"))
      (node (ref "C5") (pin "2") (pinfunction "2_2") (pintype "passive"))
      (node (ref "C50") (pin "2") (pinfunction "2_2") (pintype "passive"))
      (node (ref "C54") (pin "2") (pinfunction "2_2") (pintype "passive"))
      (node (ref "C55") (pin "2") (pinfunction "2_2") (pintype "passive"))
      (node (ref "C56") (pin "2") (pinfunction "2_2") (pintype "passive"))
      (node (ref "C57") (pin "2") (pinfunction "2_2") (pintype "passive"))
      (node (ref "C6") (pin "2") (pinfunction "2_2") (pintype "passive"))
      (node (ref "C61") (pin "2") (pinfunction "2_2") (pintype "passive"))
      (node (ref "C62") (pin "2") (pinfunction "2_2") (pintype "passive"))
      (node (ref "C63") (pin "2") (pinfunction "2_2") (pintype "passive"))
      (node (ref "C64") (pin "2") (pinfunction "2_2") (pintype "passive"))
      (node (ref "C67") (pin "2") (pinfunction "2_2") (pintype "passive"))
      (node (ref "C68") (pin "2") (pinfunction "2_2") (pintype "passive"))
      (node (ref "C69") (pin "2") (pinfunction "2_2") (pintype "passive"))
      (node (ref "C7") (pin "2") (pinfunction "2_2") (pintype "passive"))
      (node (ref "C70") (pin "2") (pinfunction "2_2") (pintype "passive"))
      (node (ref "C73") (pin "2") (pinfunction "2_2") (pintype "passive"))
      (node (ref "C74") (pin "2") (pinfunction "2_2") (pintype "passive"))
      (node (ref "C75") (pin "2") (pinfunction "2_2") (pintype "passive"))
      (node (ref "C76") (pin "2") (pinfunction "2_2") (pintype "passive"))
      (node (ref "C8") (pin "2") (pinfunction "2_2") (pintype "passive"))
      (node (ref "C9") (pin "2") (pinfunction "2_2") (pintype "passive"))
      (node (ref "R8") (pin "2") (pinfunction "2_2") (pintype "passive"))
      (node (ref "R9") (pin "2") (pinfunction "2_2") (pintype "passive"))
      (node (ref "U1") (pin "10") (pinfunction "VCC1-VCO_10") (pintype "passive"))
      (node (ref "U1") (pin "17") (pinfunction "VCC2-CG1_17") (pintype "passive"))
      (node (ref "U1") (pin "21") (pinfunction "VCC3-SYSREF_21") (pintype "passive"))
      (node (ref "U1") (pin "26") (pinfunction "VCC4-CG2_26") (pintype "passive"))
      (node (ref "U1") (pin "33") (pinfunction "VCC5-DIG_33") (pintype "passive"))
      (node (ref "U1") (pin "36") (pinfunction "VCC6-PLL1_36") (pintype "passive"))
      (node (ref "U1") (pin "39") (pinfunction "VCC7-OSCOUT_39") (pintype "passive"))
      (node (ref "U1") (pin "42") (pinfunction "VCC8-OSCIN_42") (pintype "passive"))
      (node (ref "U1") (pin "45") (pinfunction "VCC9-CP2_45") (pintype "passive"))
      (node (ref "U1") (pin "47") (pinfunction "VCC10-PLL2_47") (pintype "passive"))
      (node (ref "U1") (pin "53") (pinfunction "VCC11-CG3_53") (pintype "passive"))
      (node (ref "U1") (pin "64") (pinfunction "VCC12-CG0_64") (pintype "passive"))
      (node (ref "Y1") (pin "6") (pinfunction "Vs_6") (pintype "power_in"))
    )
    (net (code "55") (name "unconnected-(U1-DCLKOU0N-Pad2)") (class "Default")
      (node (ref "U1") (pin "2") (pinfunction "DCLKOU0N_2") (pintype "passive+no_connect"))
    )
    (net (code "56") (name "unconnected-(U1-DCLKOUT0P-Pad1)") (class "Default")
      (node (ref "U1") (pin "1") (pinfunction "DCLKOUT0P_1") (pintype "passive+no_connect"))
    )
    (net (code "57") (name "unconnected-(U1-DCLKOUT4N-Pad25)") (class "Default")
      (node (ref "U1") (pin "25") (pinfunction "DCLKOUT4N_25") (pintype "passive+no_connect"))
    )
    (net (code "58") (name "unconnected-(U1-DCLKOUT4P-Pad24)") (class "Default")
      (node (ref "U1") (pin "24") (pinfunction "DCLKOUT4P_24") (pintype "passive+no_connect"))
    )
    (net (code "59") (name "unconnected-(U1-DCLKOUT8N-Pad52)") (class "Default")
      (node (ref "U1") (pin "52") (pinfunction "DCLKOUT8N_52") (pintype "passive+no_connect"))
    )
    (net (code "60") (name "unconnected-(U1-DCLKOUT8P-Pad51)") (class "Default")
      (node (ref "U1") (pin "51") (pinfunction "DCLKOUT8P_51") (pintype "passive+no_connect"))
    )
    (net (code "61") (name "unconnected-(U1-DCLKOUT10N-Pad55)") (class "Default")
      (node (ref "U1") (pin "55") (pinfunction "DCLKOUT10N_55") (pintype "passive+no_connect"))
    )
    (net (code "62") (name "unconnected-(U1-NC-Pad7)") (class "Default")
      (node (ref "U1") (pin "7") (pinfunction "NC_7") (pintype "passive+no_connect"))
    )
    (net (code "63") (name "unconnected-(U1-NC-Pad8)") (class "Default")
      (node (ref "U1") (pin "8") (pinfunction "NC_8") (pintype "passive+no_connect"))
    )
    (net (code "64") (name "unconnected-(U1-NC-Pad9)") (class "Default")
      (node (ref "U1") (pin "9") (pinfunction "NC_9") (pintype "passive+no_connect"))
    )
    (net (code "65") (name "unconnected-(U1-OSCOUT{slash}CLKIN2N-Pad41)") (class "Default")
      (node (ref "U1") (pin "41") (pinfunction "OSCOUT/CLKIN2N_41") (pintype "passive"))
    )
    (net (code "66") (name "unconnected-(U1-OSCOUT{slash}CLKIN2P-Pad40)") (class "Default")
      (node (ref "U1") (pin "40") (pinfunction "OSCOUT/CLKIN2P_40") (pintype "passive"))
    )
    (net (code "67") (name "unconnected-(U1-SDCLKOUT1N-Pad4)") (class "Default")
      (node (ref "U1") (pin "4") (pinfunction "SDCLKOUT1N_4") (pintype "passive+no_connect"))
    )
    (net (code "68") (name "unconnected-(U1-SDCLKOUT1P-Pad3)") (class "Default")
      (node (ref "U1") (pin "3") (pinfunction "SDCLKOUT1P_3") (pintype "passive+no_connect"))
    )
    (net (code "69") (name "unconnected-(U1-SDCLKOUT3N-Pad14)") (class "Default")
      (node (ref "U1") (pin "14") (pinfunction "SDCLKOUT3N_14") (pintype "passive+no_connect"))
    )
    (net (code "70") (name "unconnected-(U1-SDCLKOUT3P-Pad13)") (class "Default")
      (node (ref "U1") (pin "13") (pinfunction "SDCLKOUT3P_13") (pintype "passive+no_connect"))
    )
    (net (code "71") (name "unconnected-(U1-SDCLKOUT5N-Pad23)") (class "Default")
      (node (ref "U1") (pin "23") (pinfunction "SDCLKOUT5N_23") (pintype "passive+no_connect"))
    )
    (net (code "72") (name "unconnected-(U1-SDCLKOUT5P-Pad22)") (class "Default")
      (node (ref "U1") (pin "22") (pinfunction "SDCLKOUT5P_22") (pintype "passive+no_connect"))
    )
    (net (code "73") (name "unconnected-(U1-SDCLKOUT7N-Pad30)") (class "Default")
      (node (ref "U1") (pin "30") (pinfunction "SDCLKOUT7N_30") (pintype "passive+no_connect"))
    )
    (net (code "74") (name "unconnected-(U1-SDCLKOUT7P-Pad29)") (class "Default")
      (node (ref "U1") (pin "29") (pinfunction "SDCLKOUT7P_29") (pintype "passive+no_connect"))
    )
    (net (code "75") (name "unconnected-(U1-SDCLKOUT9N-Pad50)") (class "Default")
      (node (ref "U1") (pin "50") (pinfunction "SDCLKOUT9N_50") (pintype "passive+no_connect"))
    )
    (net (code "76") (name "unconnected-(U1-SDCLKOUT9P-Pad49)") (class "Default")
      (node (ref "U1") (pin "49") (pinfunction "SDCLKOUT9P_49") (pintype "passive+no_connect"))
    )
    (net (code "77") (name "unconnected-(U1-SDCLKOUT11N-Pad56)") (class "Default")
      (node (ref "U1") (pin "56") (pinfunction "SDCLKOUT11N_56") (pintype "passive+no_connect"))
    )
    (net (code "78") (name "unconnected-(U1-SDCLKOUT11P-Pad57)") (class "Default")
      (node (ref "U1") (pin "57") (pinfunction "SDCLKOUT11P_57") (pintype "passive+no_connect"))
    )
    (net (code "79") (name "unconnected-(U1-SDCLKOUT13N-Pad61)") (class "Default")
      (node (ref "U1") (pin "61") (pinfunction "SDCLKOUT13N_61") (pintype "passive+no_connect"))
    )
    (net (code "80") (name "unconnected-(U1-SDCLKOUT13P-Pad60)") (class "Default")
      (node (ref "U1") (pin "60") (pinfunction "SDCLKOUT13P_60") (pintype "passive+no_connect"))
    )
  )
)
